# bvm.net
KiCad netlist of a schematic drawn in Altium Designer
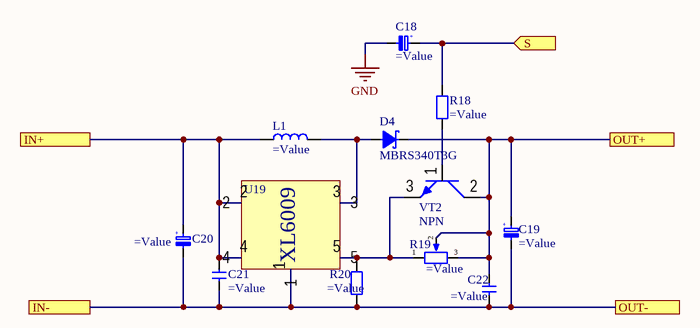
[diagram p0: bvm.SchDoc]

(export (version "E")
  (design (tool "Eeschema 10.0.6"))
  (components
    (comp (ref "C18")
      (value "~")
      (footprint "D6.6C6.6H6.1")
      (libsource (lib "AlexChistiakov") (part "Cap Electrolytic"))
    )
    (comp (ref "C19")
      (value "~")
      (footprint "D8C3.2H12")
      (libsource (lib "AlexChistiakov") (part "Cap Aluminum"))
    )
    (comp (ref "C20")
      (value "~")
      (footprint "D8C3.2H12")
      (libsource (lib "AlexChistiakov") (part "Cap Aluminum"))
    )
    (comp (ref "C21") (value "~") (footprint "cap0603") (libsource (lib "AlexChistiakov") (part "Cap SMD")))
    (comp (ref "C22") (value "~") (footprint "cap0603") (libsource (lib "AlexChistiakov") (part "Cap SMD")))
    (comp (ref "D4")
      (value "MBRS340T3G")
      (footprint "DO214AB(SMC)")
      (libsource (lib "AlexChistiakov") (part "MBRS340T3G"))
    )
    (comp (ref "L1") (value "~") (footprint "SRR1280") (libsource (lib "AlexChistiakov") (part "Inductor")))
    (comp (ref "R18")
      (value "~")
      (footprint "res0603")
      (libsource (lib "AlexChistiakov") (part "Resistor SMD"))
    )
    (comp (ref "R19")
      (value "~")
      (footprint "3224W")
      (libsource (lib "AlexChistiakov") (part "Potentiometer"))
    )
    (comp (ref "R20")
      (value "~")
      (footprint "res0603")
      (libsource (lib "AlexChistiakov") (part "Resistor SMD"))
    )
    (comp (ref "U19") (value "~") (footprint "TO263S-5+1") (libsource (lib "XL6009") (part "XL6009")))
    (comp (ref "VT2") (value "NPN") (footprint "SOT23-3_A") (libsource (lib "AlexChistiakov") (part "NPN")))
  )
  (nets
    (net (code "1") (name "/IN+") (class "Default")
      (node (ref "C20") (pin "1") (pinfunction "PLUS_1") (pintype "passive"))
      (node (ref "C21") (pin "2") (pinfunction "2_2") (pintype "passive"))
      (node (ref "L1") (pin "1") (pinfunction "1_1") (pintype "passive"))
      (node (ref "U19") (pin "2") (pinfunction "2_2") (pintype "passive"))
      (node (ref "U19") (pin "4") (pinfunction "4_4") (pintype "passive"))
    )
    (net (code "2") (name "/IN-") (class "Default")
      (node (ref "C19") (pin "2") (pinfunction "MINUS_2") (pintype "passive"))
      (node (ref "C20") (pin "2") (pinfunction "MINUS_2") (pintype "passive"))
      (node (ref "C21") (pin "1") (pinfunction "1_1") (pintype "passive"))
      (node (ref "C22") (pin "1") (pinfunction "1_1") (pintype "passive"))
      (node (ref "R20") (pin "1") (pinfunction "1_1") (pintype "passive"))
      (node (ref "U19") (pin "1") (pinfunction "1_1") (pintype "passive"))
    )
    (net (code "3") (name "/OUT+") (class "Default")
      (node (ref "C19") (pin "1") (pinfunction "PLUS_1") (pintype "passive"))
      (node (ref "C22") (pin "2") (pinfunction "2_2") (pintype "passive"))
      (node (ref "D4") (pin "2") (pinfunction "2_2") (pintype "passive"))
      (node (ref "R19") (pin "2") (pinfunction "2_2") (pintype "passive"))
      (node (ref "R19") (pin "3") (pinfunction "3_3") (pintype "passive"))
      (node (ref "VT2") (pin "2") (pinfunction "2_2") (pintype "passive"))
    )
    (net (code "4") (name "/S") (class "Default")
      (node (ref "C18") (pin "1") (pinfunction "PLUS_1") (pintype "passive"))
      (node (ref "R18") (pin "2") (pinfunction "2_2") (pintype "passive"))
    )
    (net (code "5") (name "GND") (class "Default")
      (node (ref "C18") (pin "2") (pinfunction "MINUS_2") (pintype "passive"))
    )
    (net (code "6") (name "Net-(D4-Pad1)") (class "Default")
      (node (ref "D4") (pin "1") (pinfunction "1_1") (pintype "passive"))
      (node (ref "L1") (pin "2") (pinfunction "2_2") (pintype "passive"))
      (node (ref "U19") (pin "3") (pinfunction "3_3") (pintype "passive"))
    )
    (net (code "7") (name "Net-(R18-Pad1)") (class "Default")
      (node (ref "R18") (pin "1") (pinfunction "1_1") (pintype "passive"))
      (node (ref "VT2") (pin "1") (pinfunction "1_1") (pintype "passive"))
    )
    (net (code "8") (name "Net-(R19-Pad1)") (class "Default")
      (node (ref "R19") (pin "1") (pinfunction "1_1") (pintype "passive"))
      (node (ref "R20") (pin "2") (pinfunction "2_2") (pintype "passive"))
      (node (ref "U19") (pin "5") (pinfunction "5_5") (pintype "passive"))
      (node (ref "VT2") (pin "3") (pinfunction "3_3") (pintype "passive"))
    )
  )
)
